# solenoid.net
KiCad netlist of a schematic drawn in EAGLE
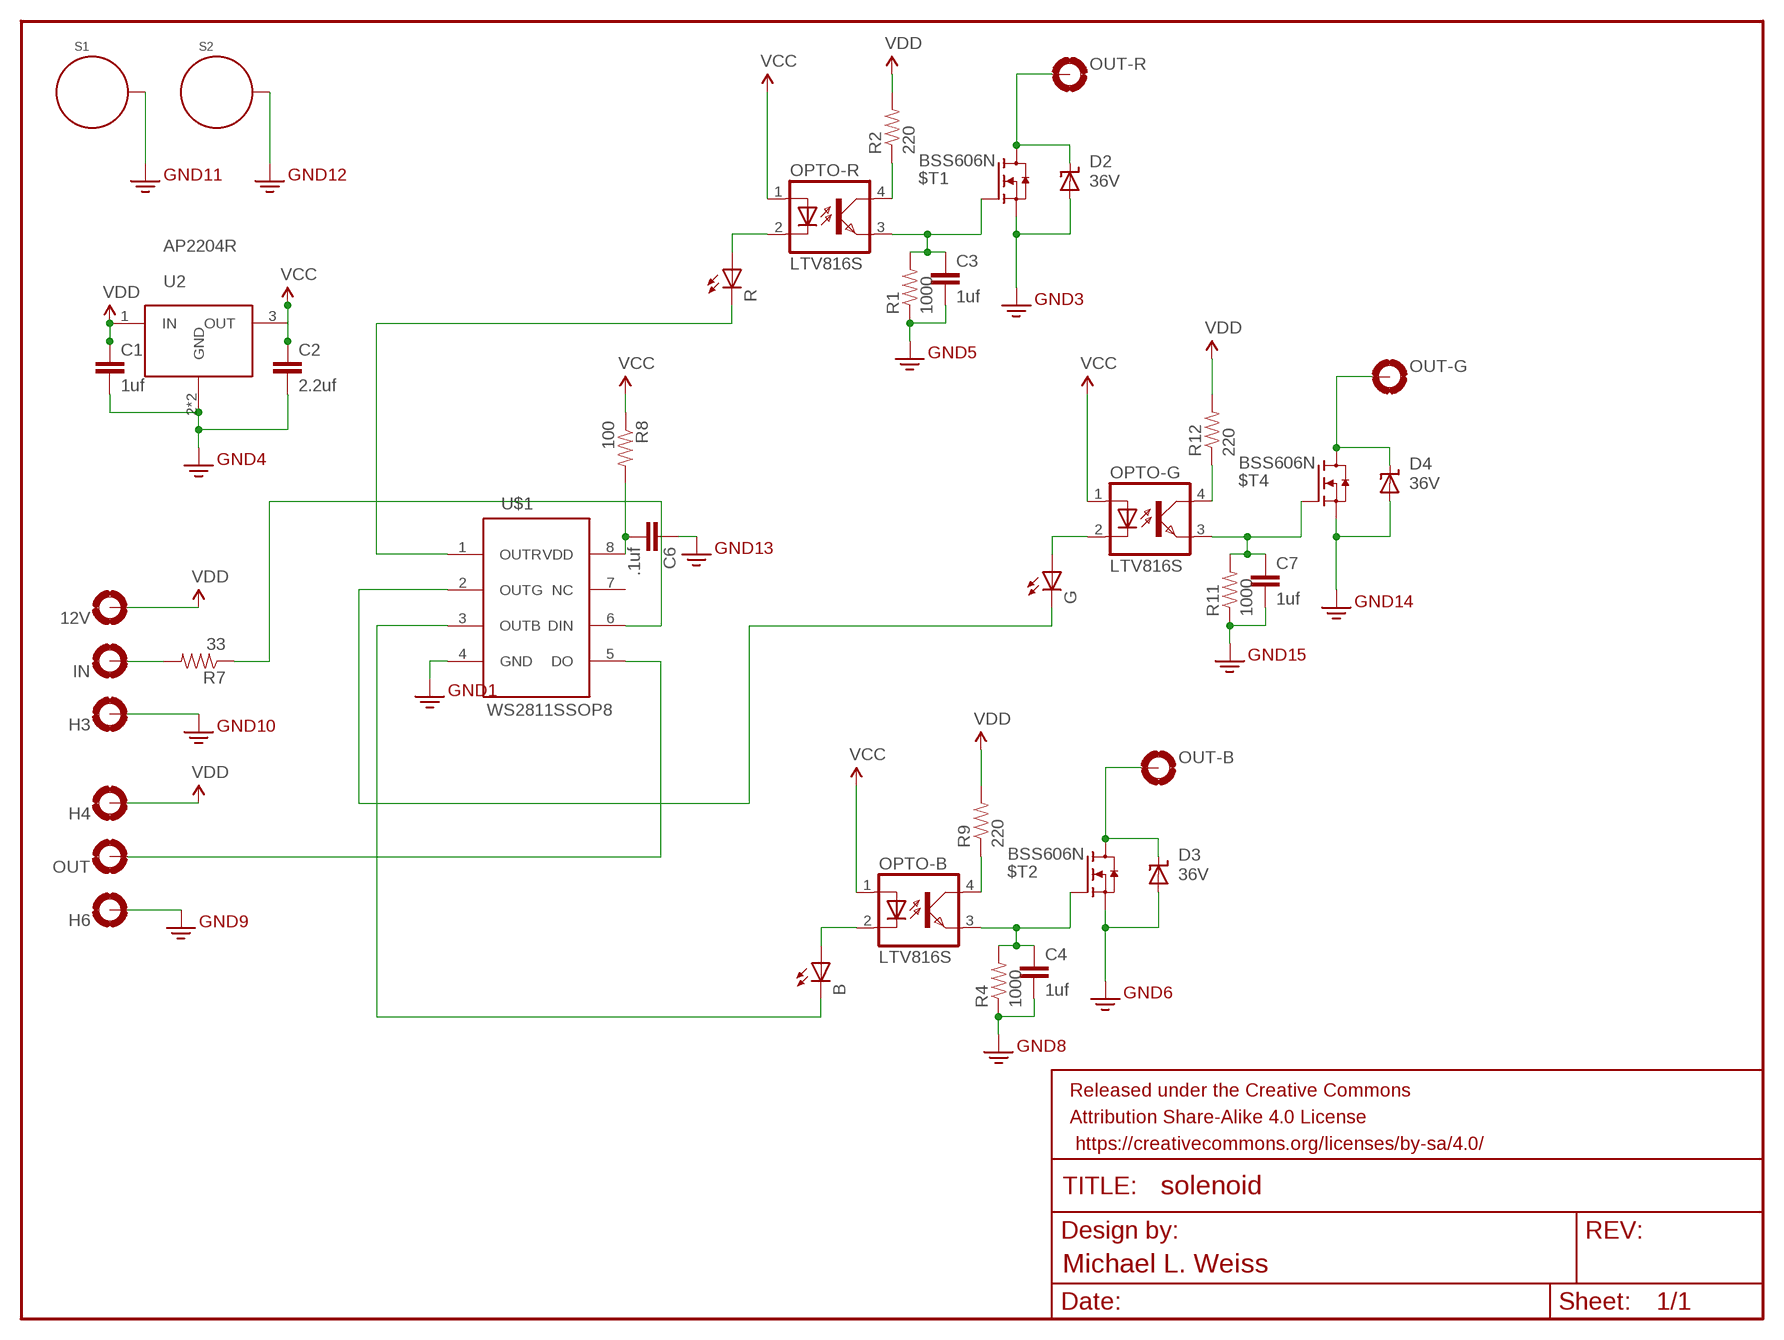
[diagram p0: schematic, sheet 1]

(export (version "E")
  (design (tool "Eeschema 10.0.6"))
  (components
    (comp (ref "$T1")
      (value "BSS606N")
      (footprint "eagle-import:SOT89R")
      (libsource (lib "eagle-import") (part "BSS606N"))
    )
    (comp (ref "$T2")
      (value "BSS606N")
      (footprint "eagle-import:SOT89R")
      (libsource (lib "eagle-import") (part "BSS606N"))
    )
    (comp (ref "$T4")
      (value "BSS606N")
      (footprint "eagle-import:SOT89R")
      (libsource (lib "eagle-import") (part "BSS606N"))
    )
    (comp (ref "12V")
      (value "MOUNT-PAD-ROUND2.8")
      (footprint "eagle-import:2,8-PAD")
      (libsource (lib "eagle-import") (part "MOUNT-PAD-ROUND2.8"))
    )
    (comp (ref "B")
      (value "LEDCHIPLED_0805")
      (footprint "eagle-import:CHIPLED_0805")
      (libsource (lib "eagle-import") (part "LEDCHIPLED_0805"))
    )
    (comp (ref "C1")
      (value "1uf")
      (footprint "eagle-import:0805")
      (libsource (lib "eagle-import") (part "CAP0805"))
    )
    (comp (ref "C2")
      (value "2.2uf")
      (footprint "eagle-import:0805")
      (libsource (lib "eagle-import") (part "CAP0805"))
    )
    (comp (ref "C3")
      (value "1uf")
      (footprint "eagle-import:0805")
      (libsource (lib "eagle-import") (part "CAP0805"))
    )
    (comp (ref "C4")
      (value "1uf")
      (footprint "eagle-import:0805")
      (libsource (lib "eagle-import") (part "CAP0805"))
    )
    (comp (ref "C6")
      (value ".1uf")
      (footprint "eagle-import:0805")
      (libsource (lib "eagle-import") (part "CAP0805"))
    )
    (comp (ref "C7")
      (value "1uf")
      (footprint "eagle-import:0805")
      (libsource (lib "eagle-import") (part "CAP0805"))
    )
    (comp (ref "D2")
      (value "36V")
      (footprint "eagle-import:SMBJ")
      (libsource (lib "eagle-import") (part "SUPPRESSOR-SMBJ"))
    )
    (comp (ref "D3")
      (value "36V")
      (footprint "eagle-import:SMBJ")
      (libsource (lib "eagle-import") (part "SUPPRESSOR-SMBJ"))
    )
    (comp (ref "D4")
      (value "36V")
      (footprint "eagle-import:SMBJ")
      (libsource (lib "eagle-import") (part "SUPPRESSOR-SMBJ"))
    )
    (comp (ref "FRAME1")
      (value "FRAME-LETTERNO_PACKAGE")
      (footprint "eagle-import:DUMMY")
      (fields
        (field (name "CREVISON") "1.1")
        (field (name "DESIGNER") "Michael L. Weiss")
        (field (name "VERSION") "v1.0")
      )
      (libsource (lib "eagle-import") (part "FRAME-LETTERNO_PACKAGE"))
    )
    (comp (ref "G")
      (value "LEDCHIPLED_0805")
      (footprint "eagle-import:CHIPLED_0805")
      (libsource (lib "eagle-import") (part "LEDCHIPLED_0805"))
    )
    (comp (ref "H3")
      (value "MOUNT-PAD-ROUND2.8")
      (footprint "eagle-import:2,8-PAD")
      (libsource (lib "eagle-import") (part "MOUNT-PAD-ROUND2.8"))
    )
    (comp (ref "H4")
      (value "MOUNT-PAD-ROUND2.8")
      (footprint "eagle-import:2,8-PAD")
      (libsource (lib "eagle-import") (part "MOUNT-PAD-ROUND2.8"))
    )
    (comp (ref "H6")
      (value "MOUNT-PAD-ROUND2.8")
      (footprint "eagle-import:2,8-PAD")
      (libsource (lib "eagle-import") (part "MOUNT-PAD-ROUND2.8"))
    )
    (comp (ref "IN")
      (value "MOUNT-PAD-ROUND2.8")
      (footprint "eagle-import:2,8-PAD")
      (libsource (lib "eagle-import") (part "MOUNT-PAD-ROUND2.8"))
    )
    (comp (ref "OPTO-B")
      (value "LTV816S")
      (footprint "eagle-import:DIL4-SMD")
      (libsource (lib "eagle-import") (part "LTV816S"))
    )
    (comp (ref "OPTO-G")
      (value "LTV816S")
      (footprint "eagle-import:DIL4-SMD")
      (libsource (lib "eagle-import") (part "LTV816S"))
    )
    (comp (ref "OPTO-R")
      (value "LTV816S")
      (footprint "eagle-import:DIL4-SMD")
      (libsource (lib "eagle-import") (part "LTV816S"))
    )
    (comp (ref "OUT")
      (value "MOUNT-PAD-ROUND2.8")
      (footprint "eagle-import:2,8-PAD")
      (libsource (lib "eagle-import") (part "MOUNT-PAD-ROUND2.8"))
    )
    (comp (ref "OUT-B")
      (value "MOUNT-PAD-ROUND2.8")
      (footprint "eagle-import:2,8-PAD")
      (libsource (lib "eagle-import") (part "MOUNT-PAD-ROUND2.8"))
    )
    (comp (ref "OUT-G")
      (value "MOUNT-PAD-ROUND2.8")
      (footprint "eagle-import:2,8-PAD")
      (libsource (lib "eagle-import") (part "MOUNT-PAD-ROUND2.8"))
    )
    (comp (ref "OUT-R")
      (value "MOUNT-PAD-ROUND2.8")
      (footprint "eagle-import:2,8-PAD")
      (libsource (lib "eagle-import") (part "MOUNT-PAD-ROUND2.8"))
    )
    (comp (ref "R")
      (value "LEDCHIPLED_0805")
      (footprint "eagle-import:CHIPLED_0805")
      (libsource (lib "eagle-import") (part "LEDCHIPLED_0805"))
    )
    (comp (ref "R1")
      (value "1000")
      (footprint "eagle-import:0805")
      (libsource (lib "eagle-import") (part "RESISTOR0805-RES"))
    )
    (comp (ref "R2")
      (value "220")
      (footprint "eagle-import:0805")
      (libsource (lib "eagle-import") (part "RESISTOR0805-RES"))
    )
    (comp (ref "R4")
      (value "1000")
      (footprint "eagle-import:0805")
      (libsource (lib "eagle-import") (part "RESISTOR0805-RES"))
    )
    (comp (ref "R7")
      (value "33")
      (footprint "eagle-import:0805")
      (libsource (lib "eagle-import") (part "RESISTOR0805-RES"))
    )
    (comp (ref "R8")
      (value "100")
      (footprint "eagle-import:0805")
      (libsource (lib "eagle-import") (part "RESISTOR0805-RES"))
    )
    (comp (ref "R9")
      (value "220")
      (footprint "eagle-import:0805")
      (libsource (lib "eagle-import") (part "RESISTOR0805-RES"))
    )
    (comp (ref "R11")
      (value "1000")
      (footprint "eagle-import:0805")
      (libsource (lib "eagle-import") (part "RESISTOR0805-RES"))
    )
    (comp (ref "R12")
      (value "220")
      (footprint "eagle-import:0805")
      (libsource (lib "eagle-import") (part "RESISTOR0805-RES"))
    )
    (comp (ref "S1")
      (value "STANDOFF_ELECTRICAL")
      (footprint "eagle-import:STANDOFF-ELECTRICAL")
      (libsource (lib "eagle-import") (part "STANDOFF_ELECTRICAL"))
    )
    (comp (ref "S2")
      (value "STANDOFF_ELECTRICAL")
      (footprint "eagle-import:STANDOFF-ELECTRICAL")
      (libsource (lib "eagle-import") (part "STANDOFF_ELECTRICAL"))
    )
    (comp (ref "U$1")
      (value "WS2811SSOP8")
      (footprint "eagle-import:SOIC8_150MIL")
      (libsource (lib "eagle-import") (part "WS2811SSOP8"))
    )
    (comp (ref "U2")
      (value "AP2204R")
      (footprint "eagle-import:SOT89R")
      (fields (field (name "VOLTAGE") "5.0"))
      (libsource (lib "eagle-import") (part "AP2204R"))
    )
  )
  (nets
    (net (code "1") (name "GND2") (class "Default")
      (node (ref "$T1") (pin "3") (pinfunction "S_3") (pintype "passive"))
      (node (ref "$T2") (pin "3") (pinfunction "S_3") (pintype "passive"))
      (node (ref "$T4") (pin "3") (pinfunction "S_3") (pintype "passive"))
      (node (ref "C1") (pin "2") (pinfunction "2_2") (pintype "passive"))
      (node (ref "C2") (pin "2") (pinfunction "2_2") (pintype "passive"))
      (node (ref "C3") (pin "2") (pinfunction "2_2") (pintype "passive"))
      (node (ref "C4") (pin "2") (pinfunction "2_2") (pintype "passive"))
      (node (ref "C6") (pin "1") (pinfunction "1_1") (pintype "passive"))
      (node (ref "C7") (pin "2") (pinfunction "2_2") (pintype "passive"))
      (node (ref "D2") (pin "A") (pinfunction "A_A") (pintype "passive"))
      (node (ref "D3") (pin "A") (pinfunction "A_A") (pintype "passive"))
      (node (ref "D4") (pin "A") (pinfunction "A_A") (pintype "passive"))
      (node (ref "H3") (pin "B2,8") (pinfunction "MOUNT_B2,8") (pintype "passive"))
      (node (ref "H6") (pin "B2,8") (pinfunction "MOUNT_B2,8") (pintype "passive"))
      (node (ref "R1") (pin "1") (pinfunction "1_1") (pintype "passive"))
      (node (ref "R11") (pin "1") (pinfunction "1_1") (pintype "passive"))
      (node (ref "R4") (pin "1") (pinfunction "1_1") (pintype "passive"))
      (node (ref "S1") (pin "P1") (pinfunction "P$1_P1") (pintype "bidirectional"))
      (node (ref "S2") (pin "P1") (pinfunction "P$1_P1") (pintype "bidirectional"))
      (node (ref "U$1") (pin "4") (pinfunction "GND_4") (pintype "power_in"))
      (node (ref "U2") (pin "2") (pinfunction "GND_2") (pintype "power_in"))
      (node (ref "U2") (pin "4") (pinfunction "GND_4") (pintype "power_in"))
    )
    (net (code "2") (name "Net-($T1-G)") (class "Default")
      (node (ref "$T1") (pin "1") (pinfunction "G_1") (pintype "passive"))
      (node (ref "C3") (pin "1") (pinfunction "1_1") (pintype "passive"))
      (node (ref "OPTO-R") (pin "3") (pinfunction "EMIT_3") (pintype "passive"))
      (node (ref "R1") (pin "2") (pinfunction "2_2") (pintype "passive"))
    )
    (net (code "3") (name "Net-($T2-G)") (class "Default")
      (node (ref "$T2") (pin "1") (pinfunction "G_1") (pintype "passive"))
      (node (ref "C4") (pin "1") (pinfunction "1_1") (pintype "passive"))
      (node (ref "OPTO-B") (pin "3") (pinfunction "EMIT_3") (pintype "passive"))
      (node (ref "R4") (pin "2") (pinfunction "2_2") (pintype "passive"))
    )
    (net (code "4") (name "Net-($T4-G)") (class "Default")
      (node (ref "$T4") (pin "1") (pinfunction "G_1") (pintype "passive"))
      (node (ref "C7") (pin "1") (pinfunction "1_1") (pintype "passive"))
      (node (ref "OPTO-G") (pin "3") (pinfunction "EMIT_3") (pintype "passive"))
      (node (ref "R11") (pin "2") (pinfunction "2_2") (pintype "passive"))
    )
    (net (code "5") (name "Net-(IN-MOUNT)") (class "Default")
      (node (ref "IN") (pin "B2,8") (pinfunction "MOUNT_B2,8") (pintype "passive"))
      (node (ref "R7") (pin "2") (pinfunction "2_2") (pintype "passive"))
    )
    (net (code "6") (name "Net-(OPTO-B-C)") (class "Default")
      (node (ref "B") (pin "A") (pinfunction "A_A") (pintype "passive"))
      (node (ref "OPTO-B") (pin "2") (pinfunction "C_2") (pintype "passive"))
    )
    (net (code "7") (name "Net-(OPTO-B-COL)") (class "Default")
      (node (ref "OPTO-B") (pin "4") (pinfunction "COL_4") (pintype "passive"))
      (node (ref "R9") (pin "1") (pinfunction "1_1") (pintype "passive"))
    )
    (net (code "8") (name "Net-(OPTO-G-C)") (class "Default")
      (node (ref "G") (pin "A") (pinfunction "A_A") (pintype "passive"))
      (node (ref "OPTO-G") (pin "2") (pinfunction "C_2") (pintype "passive"))
    )
    (net (code "9") (name "Net-(OPTO-G-COL)") (class "Default")
      (node (ref "OPTO-G") (pin "4") (pinfunction "COL_4") (pintype "passive"))
      (node (ref "R12") (pin "1") (pinfunction "1_1") (pintype "passive"))
    )
    (net (code "10") (name "Net-(OPTO-R-C)") (class "Default")
      (node (ref "OPTO-R") (pin "2") (pinfunction "C_2") (pintype "passive"))
      (node (ref "R") (pin "A") (pinfunction "A_A") (pintype "passive"))
    )
    (net (code "11") (name "Net-(OPTO-R-COL)") (class "Default")
      (node (ref "OPTO-R") (pin "4") (pinfunction "COL_4") (pintype "passive"))
      (node (ref "R2") (pin "1") (pinfunction "1_1") (pintype "passive"))
    )
    (net (code "12") (name "Net-(OUT-B-MOUNT)") (class "Default")
      (node (ref "$T2") (pin "2") (pinfunction "D_2") (pintype "passive"))
      (node (ref "$T2") (pin "4") (pinfunction "D_4") (pintype "passive"))
      (node (ref "D3") (pin "C") (pinfunction "C_C") (pintype "passive"))
      (node (ref "OUT-B") (pin "B2,8") (pinfunction "MOUNT_B2,8") (pintype "passive"))
    )
    (net (code "13") (name "Net-(OUT-G-MOUNT)") (class "Default")
      (node (ref "$T4") (pin "2") (pinfunction "D_2") (pintype "passive"))
      (node (ref "$T4") (pin "4") (pinfunction "D_4") (pintype "passive"))
      (node (ref "D4") (pin "C") (pinfunction "C_C") (pintype "passive"))
      (node (ref "OUT-G") (pin "B2,8") (pinfunction "MOUNT_B2,8") (pintype "passive"))
    )
    (net (code "14") (name "Net-(OUT-MOUNT)") (class "Default")
      (node (ref "OUT") (pin "B2,8") (pinfunction "MOUNT_B2,8") (pintype "passive"))
      (node (ref "U$1") (pin "5") (pinfunction "DO_5") (pintype "output"))
    )
    (net (code "15") (name "Net-(OUT-R-MOUNT)") (class "Default")
      (node (ref "$T1") (pin "2") (pinfunction "D_2") (pintype "passive"))
      (node (ref "$T1") (pin "4") (pinfunction "D_4") (pintype "passive"))
      (node (ref "D2") (pin "C") (pinfunction "C_C") (pintype "passive"))
      (node (ref "OUT-R") (pin "B2,8") (pinfunction "MOUNT_B2,8") (pintype "passive"))
    )
    (net (code "16") (name "Net-(U$1-DIN)") (class "Default")
      (node (ref "R7") (pin "1") (pinfunction "1_1") (pintype "passive"))
      (node (ref "U$1") (pin "6") (pinfunction "DIN_6") (pintype "input"))
    )
    (net (code "17") (name "Net-(U$1-OUTB)") (class "Default")
      (node (ref "B") (pin "C") (pinfunction "C_C") (pintype "passive"))
      (node (ref "U$1") (pin "3") (pinfunction "OUTB_3") (pintype "output"))
    )
    (net (code "18") (name "Net-(U$1-OUTG)") (class "Default")
      (node (ref "G") (pin "C") (pinfunction "C_C") (pintype "passive"))
      (node (ref "U$1") (pin "2") (pinfunction "OUTG_2") (pintype "output"))
    )
    (net (code "19") (name "Net-(U$1-OUTR)") (class "Default")
      (node (ref "R") (pin "C") (pinfunction "C_C") (pintype "passive"))
      (node (ref "U$1") (pin "1") (pinfunction "OUTR_1") (pintype "output"))
    )
    (net (code "20") (name "Net-(U$1-VDD)") (class "Default")
      (node (ref "C6") (pin "2") (pinfunction "2_2") (pintype "passive"))
      (node (ref "R8") (pin "2") (pinfunction "2_2") (pintype "passive"))
      (node (ref "U$1") (pin "8") (pinfunction "VDD_8") (pintype "power_in"))
    )
    (net (code "21") (name "VCC") (class "Default")
      (node (ref "C2") (pin "1") (pinfunction "1_1") (pintype "passive"))
      (node (ref "OPTO-B") (pin "1") (pinfunction "A_1") (pintype "passive"))
      (node (ref "OPTO-G") (pin "1") (pinfunction "A_1") (pintype "passive"))
      (node (ref "OPTO-R") (pin "1") (pinfunction "A_1") (pintype "passive"))
      (node (ref "R8") (pin "1") (pinfunction "1_1") (pintype "passive"))
      (node (ref "U2") (pin "3") (pinfunction "OUT_3") (pintype "power_in"))
    )
    (net (code "22") (name "VDD") (class "Default")
      (node (ref "12V") (pin "B2,8") (pinfunction "MOUNT_B2,8") (pintype "passive"))
      (node (ref "C1") (pin "1") (pinfunction "1_1") (pintype "passive"))
      (node (ref "H4") (pin "B2,8") (pinfunction "MOUNT_B2,8") (pintype "passive"))
      (node (ref "R12") (pin "2") (pinfunction "2_2") (pintype "passive"))
      (node (ref "R2") (pin "2") (pinfunction "2_2") (pintype "passive"))
      (node (ref "R9") (pin "2") (pinfunction "2_2") (pintype "passive"))
      (node (ref "U2") (pin "1") (pinfunction "IN_1") (pintype "power_in"))
    )
    (net (code "23") (name "unconnected-(U$1-NC-Pad7)") (class "Default")
      (node (ref "U$1") (pin "7") (pinfunction "NC_7") (pintype "no_connect"))
    )
  )
)
